# Sheet1.net
KiCad netlist of a schematic drawn in Altium Designer
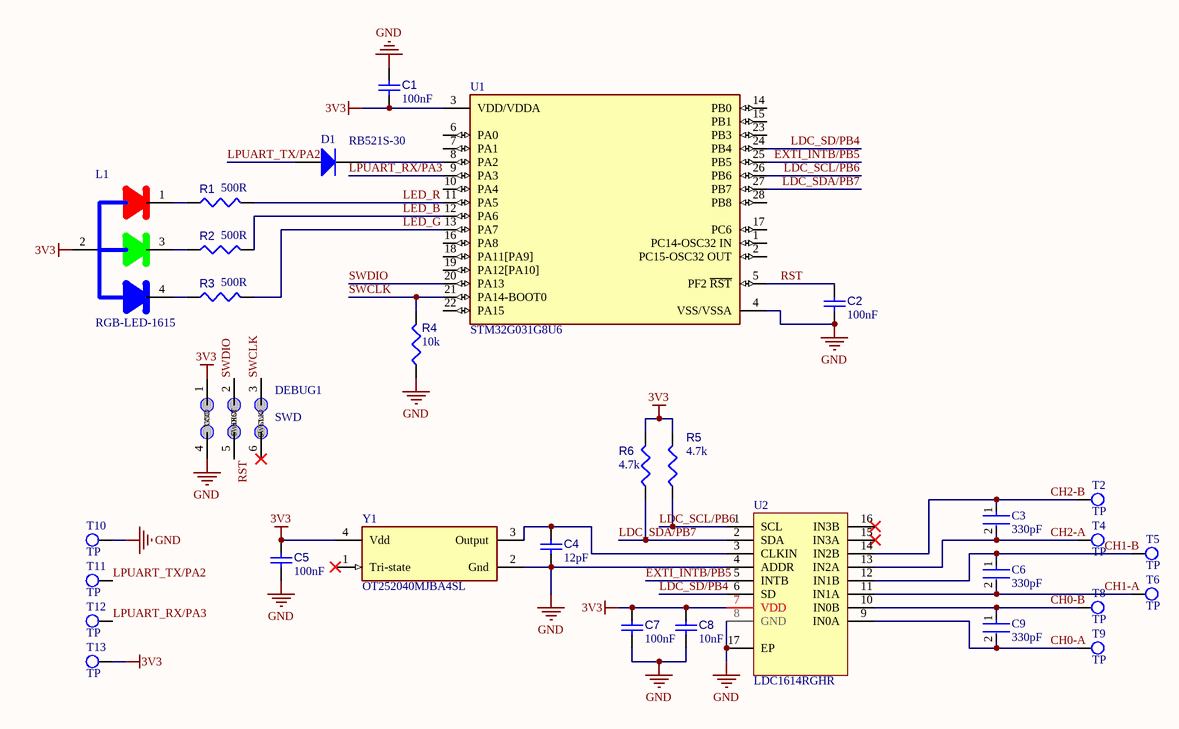
[diagram p0: Sheet1.SchDoc]

(export (version "E")
  (design (tool "Eeschema 10.0.6"))
  (components
    (comp (ref "C1")
      (value "100nF")
      (footprint "CAPC0402(1005)60_L")
      (description "Chip Capacitor, 100nF +/-20%, 10V, 0402, Thickness 0.6 mm")
      (fields (field (name "TOLERANCE") "20%") (field (name "Comment") "Capacitor 100nF +/-20% 10V 0402"))
      (libsource (lib "DigiPCBA Workspace") (part "CAP-NP-2"))
    )
    (comp (ref "C2")
      (value "100nF")
      (footprint "CAPC0402(1005)60_L")
      (description "Chip Capacitor, 100nF +/-20%, 10V, 0402, Thickness 0.6 mm")
      (fields (field (name "TOLERANCE") "20%") (field (name "Comment") "Capacitor 100nF +/-20% 10V 0402"))
      (libsource (lib "DigiPCBA Workspace") (part "CAP-NP-2"))
    )
    (comp (ref "C3")
      (value "330pF")
      (footprint "FP-C0201-AB-MFG")
      (description "C0201 18 pF C0G 30ppm/°C 5.00% 25 V")
      (fields (field (name "MANUFACTURER PART NUMBER") "C0201C180J3GACTU"))
      (libsource (lib "Altium Content Vault") (part "11868f565c42a9108669ba33697ecf6"))
    )
    (comp (ref "C4")
      (value "12pF")
      (footprint "CAPC0402(1005)33_L")
      (description "Chip Capacitor, 12pF +/-10%, 50V, 0402, Thickness 0.33 mm")
      (fields (field (name "TOLERANCE") "20%") (field (name "Comment") "Capacitor 12pF +/-10% 50V 0402"))
      (libsource (lib "DigiPCBA Workspace") (part "CAP-NP-2"))
    )
    (comp (ref "C5")
      (value "100nF")
      (footprint "CAPC0402(1005)60_L")
      (description "Chip Capacitor, 100nF +/-20%, 10V, 0402, Thickness 0.6 mm")
      (fields (field (name "TOLERANCE") "20%") (field (name "Comment") "Capacitor 100nF +/-20% 10V 0402"))
      (libsource (lib "DigiPCBA Workspace") (part "CAP-NP-2"))
    )
    (comp (ref "C6")
      (value "330pF")
      (footprint "FP-C0201-AB-MFG")
      (description "C0201 18 pF C0G 30ppm/°C 5.00% 25 V")
      (fields (field (name "MANUFACTURER PART NUMBER") "C0201C180J3GACTU"))
      (libsource (lib "Altium Content Vault") (part "11868f565c42a9108669ba33697ecf6"))
    )
    (comp (ref "C7")
      (value "100nF")
      (footprint "CAPC0402(1005)60_L")
      (description "Chip Capacitor, 100nF +/-20%, 10V, 0402, Thickness 0.6 mm")
      (fields (field (name "TOLERANCE") "20%") (field (name "Comment") "Capacitor 100nF +/-20% 10V 0402"))
      (libsource (lib "DigiPCBA Workspace") (part "CAP-NP-2"))
    )
    (comp (ref "C8")
      (value "10nF")
      (footprint "CAPC0402(1005)60_L")
      (description "Chip Capacitor, 100nF +/-20%, 10V, 0402, Thickness 0.6 mm")
      (fields (field (name "TOLERANCE") "20%") (field (name "Comment") "Capacitor 100nF +/-20% 10V 0402"))
      (libsource (lib "DigiPCBA Workspace") (part "CAP-NP-2"))
    )
    (comp (ref "C9")
      (value "330pF")
      (footprint "FP-C0201-AB-MFG")
      (description "C0201 18 pF C0G 30ppm/°C 5.00% 25 V")
      (fields (field (name "MANUFACTURER PART NUMBER") "C0201C180J3GACTU"))
      (libsource (lib "Altium Content Vault") (part "11868f565c42a9108669ba33697ecf6"))
    )
    (comp (ref "D1")
      (value "RB521S-30")
      (footprint "DIOD-SOD523-2_V")
      (description "Surface Mount Fast Switching Diode, -65 to 150 degC, 2-Pin SOD523, RoHS, Tape and Reel")
      (fields (field (name "PARTNUMBER") "1N4148WT") (field (name "MANUFACTURER") "Diodes Inc"))
      (libsource (lib "Altium Content Vault") (part "D-AK-2"))
    )
    (comp (ref "DEBUG1")
      (value "SWD")
      (footprint "DEBUG-2x3P-1.27mm Pitch")
      (description "弹簧探针烧录/调试触点")
      (libsource (lib "LG_Integrated_Library") (part "DEBUG-PogoPin-2x6P"))
    )
    (comp (ref "L1")
      (value "RGB-LED-1615")
      (footprint "RGB-LED-1615-Footprint-1")
      (description "RGB LED")
      (libsource (lib "DigiPCBA Workspace") (part "RGB-LED-1615-Symbol-1"))
    )
    (comp (ref "R1")
      (value "500R")
      (footprint "RESC0402(1005)_L")
      (description "Chip Resistor, 100 Ohms, +/-1 %, 63 mW, -55 to 155 degC, 0402")
      (fields (field (name "POWER") "63mW") (field (name "TOLERANCE") "1%"))
      (libsource (lib "DigiPCBA Workspace") (part "RES-2"))
    )
    (comp (ref "R2")
      (value "500R")
      (footprint "RESC0402(1005)_L")
      (description "Chip Resistor, 100 Ohms, +/-1 %, 63 mW, -55 to 155 degC, 0402")
      (fields (field (name "POWER") "63mW") (field (name "TOLERANCE") "1%"))
      (libsource (lib "DigiPCBA Workspace") (part "RES-2"))
    )
    (comp (ref "R3")
      (value "500R")
      (footprint "RESC0402(1005)_L")
      (description "Chip Resistor, 100 Ohms, +/-1 %, 63 mW, -55 to 155 degC, 0402")
      (fields (field (name "POWER") "63mW") (field (name "TOLERANCE") "1%"))
      (libsource (lib "DigiPCBA Workspace") (part "RES-2"))
    )
    (comp (ref "R4")
      (value "10k")
      (footprint "RESC0402(1005)_L")
      (description "Chip Resistor, 10 kOhms, +/-1 %, 63 mW, -55 to 125 degC, 0402")
      (fields (field (name "POWER") "63mW") (field (name "TOLERANCE") "1%"))
      (libsource (lib "DigiPCBA Workspace") (part "RES-2"))
    )
    (comp (ref "R5")
      (value "4.7k")
      (footprint "RESC0402(1005)_L")
      (description "Chip Resistor, 4,7 kOhms, +/-1 %, 63 mW, -55 to 155 degC, 0402")
      (fields (field (name "POWER") "63mW") (field (name "TOLERANCE") "1%"))
      (libsource (lib "DigiPCBA Workspace") (part "RES-2"))
    )
    (comp (ref "R6")
      (value "4.7k")
      (footprint "RESC0402(1005)_L")
      (description "Chip Resistor, 4,7 kOhms, +/-1 %, 63 mW, -55 to 155 degC, 0402")
      (fields (field (name "POWER") "63mW") (field (name "TOLERANCE") "1%"))
      (libsource (lib "DigiPCBA Workspace") (part "RES-2"))
    )
    (comp (ref "T2")
      (value "TP")
      (footprint "TESTPOINT-Rectangle-1.5x3")
      (description "TestPoint")
      (libsource (lib "LGSchlib") (part "TestPoint"))
    )
    (comp (ref "T4")
      (value "TP")
      (footprint "TESTPOINT-Rectangle-1.5x3")
      (description "TestPoint")
      (libsource (lib "LGSchlib") (part "TestPoint"))
    )
    (comp (ref "T5")
      (value "TP")
      (footprint "TESTPOINT-Rectangle-1.5x3")
      (description "TestPoint")
      (libsource (lib "LGSchlib") (part "TestPoint"))
    )
    (comp (ref "T6")
      (value "TP")
      (footprint "TESTPOINT-Rectangle-1.5x3")
      (description "TestPoint")
      (libsource (lib "LGSchlib") (part "TestPoint"))
    )
    (comp (ref "T8")
      (value "TP")
      (footprint "TESTPOINT-Rectangle-1.5x3")
      (description "TestPoint")
      (libsource (lib "LGSchlib") (part "TestPoint"))
    )
    (comp (ref "T9")
      (value "TP")
      (footprint "TESTPOINT-Rectangle-1.5x3")
      (description "TestPoint")
      (libsource (lib "LGSchlib") (part "TestPoint"))
    )
    (comp (ref "T10")
      (value "TP")
      (footprint "TESTPOINT-Rectangle-1.5x3")
      (description "TestPoint")
      (libsource (lib "LGSchlib") (part "TestPoint"))
    )
    (comp (ref "T11")
      (value "TP")
      (footprint "TESTPOINT-Rectangle-1.5x3")
      (description "TestPoint")
      (libsource (lib "LGSchlib") (part "TestPoint"))
    )
    (comp (ref "T12")
      (value "TP")
      (footprint "TESTPOINT-Rectangle-1.5x3")
      (description "TestPoint")
      (libsource (lib "LGSchlib") (part "TestPoint"))
    )
    (comp (ref "T13")
      (value "TP")
      (footprint "TESTPOINT-Rectangle-1.5x3")
      (description "TestPoint")
      (libsource (lib "LGSchlib") (part "TestPoint"))
    )
    (comp (ref "U1")
      (value "STM32G031G8U6")
      (footprint "FP-UFQFPN28-A0B0-MFG")
      (description "MCU 32-Bit ARM Cortex-M0+ RISC 64KB Flash 1.7V to 3.6V 28-Pin UFQFPN Tray")
      (libsource (lib "DigiPCBA Workspace") (part "fbee28bf9b321b2a381fb3d89db5bd4"))
    )
    (comp (ref "U2")
      (value "LDC1614RGHR")
      (footprint "LDC1614RGHR-Footprint-1")
      (description "4-Ch, 28-bit, high-resolution Inductance to digital converter 16-WQFN -40 to 125")
      (libsource (lib "DigiPCBA Workspace") (part "LDC1614RGHR"))
    )
    (comp (ref "Y1")
      (value "OT252040MJBA4SL")
      (footprint "FP-ECS-TXO-2520-MFG")
      (description "XTAL OSC TCXO 25.0000MHZ HCMOS")
      (libsource (lib "Altium Content Vault") (part "04cd953f3cf158082f8c09fbdb924ef"))
    )
  )
  (nets
    (net (code "1") (name "/CH0-A") (class "Default")
      (node (ref "C9") (pin "2") (pinfunction "2_2") (pintype "passive"))
      (node (ref "T9") (pin "1") (pinfunction "1_1") (pintype "passive"))
      (node (ref "U2") (pin "9") (pinfunction "IN0A_9") (pintype "passive"))
    )
    (net (code "2") (name "/CH0-B") (class "Default")
      (node (ref "C9") (pin "1") (pinfunction "1_1") (pintype "passive"))
      (node (ref "T8") (pin "1") (pinfunction "1_1") (pintype "passive"))
      (node (ref "U2") (pin "10") (pinfunction "IN0B_10") (pintype "passive"))
    )
    (net (code "3") (name "/CH1-A") (class "Default")
      (node (ref "C6") (pin "2") (pinfunction "2_2") (pintype "passive"))
      (node (ref "T6") (pin "1") (pinfunction "1_1") (pintype "passive"))
      (node (ref "U2") (pin "11") (pinfunction "IN1A_11") (pintype "passive"))
    )
    (net (code "4") (name "/CH1-B") (class "Default")
      (node (ref "C6") (pin "1") (pinfunction "1_1") (pintype "passive"))
      (node (ref "T5") (pin "1") (pinfunction "1_1") (pintype "passive"))
      (node (ref "U2") (pin "12") (pinfunction "IN1B_12") (pintype "passive"))
    )
    (net (code "5") (name "/CH2-A") (class "Default")
      (node (ref "C3") (pin "2") (pinfunction "2_2") (pintype "passive"))
      (node (ref "T4") (pin "1") (pinfunction "1_1") (pintype "passive"))
      (node (ref "U2") (pin "13") (pinfunction "IN2A_13") (pintype "passive"))
    )
    (net (code "6") (name "/CH2-B") (class "Default")
      (node (ref "C3") (pin "1") (pinfunction "1_1") (pintype "passive"))
      (node (ref "T2") (pin "1") (pinfunction "1_1") (pintype "passive"))
      (node (ref "U2") (pin "14") (pinfunction "IN2B_14") (pintype "passive"))
    )
    (net (code "7") (name "/EXTI_INTB{slash}PB5") (class "Default")
      (node (ref "U1") (pin "25") (pinfunction "PB5_25") (pintype "bidirectional"))
      (node (ref "U2") (pin "5") (pinfunction "INTB_5") (pintype "passive"))
    )
    (net (code "8") (name "/LDC_SCL{slash}PB6") (class "Default")
      (node (ref "R5") (pin "1") (pinfunction "1_1") (pintype "passive"))
      (node (ref "U1") (pin "26") (pinfunction "PB6_26") (pintype "bidirectional"))
      (node (ref "U2") (pin "1") (pinfunction "SCL_1") (pintype "passive"))
    )
    (net (code "9") (name "/LDC_SDA{slash}PB7") (class "Default")
      (node (ref "R6") (pin "1") (pinfunction "1_1") (pintype "passive"))
      (node (ref "U1") (pin "27") (pinfunction "PB7_27") (pintype "bidirectional"))
      (node (ref "U2") (pin "2") (pinfunction "SDA_2") (pintype "passive"))
    )
    (net (code "10") (name "/LDC_SD{slash}PB4") (class "Default")
      (node (ref "U1") (pin "24") (pinfunction "PB4_24") (pintype "bidirectional"))
      (node (ref "U2") (pin "6") (pinfunction "SD_6") (pintype "passive"))
    )
    (net (code "11") (name "/LED_B") (class "Default")
      (node (ref "R2") (pin "2") (pinfunction "2_2") (pintype "passive"))
      (node (ref "U1") (pin "12") (pinfunction "PA6_12") (pintype "bidirectional"))
    )
    (net (code "12") (name "/LED_G") (class "Default")
      (node (ref "R3") (pin "2") (pinfunction "2_2") (pintype "passive"))
      (node (ref "U1") (pin "13") (pinfunction "PA7_13") (pintype "bidirectional"))
    )
    (net (code "13") (name "/LED_R") (class "Default")
      (node (ref "R1") (pin "2") (pinfunction "2_2") (pintype "passive"))
      (node (ref "U1") (pin "11") (pinfunction "PA5_11") (pintype "bidirectional"))
    )
    (net (code "14") (name "/LPUART_RX{slash}PA3") (class "Default")
      (node (ref "T12") (pin "1") (pinfunction "1_1") (pintype "passive"))
      (node (ref "U1") (pin "9") (pinfunction "PA3_9") (pintype "bidirectional"))
    )
    (net (code "15") (name "/LPUART_TX{slash}PA2") (class "Default")
      (node (ref "D1") (pin "1") (pinfunction "A_1") (pintype "passive"))
      (node (ref "T11") (pin "1") (pinfunction "1_1") (pintype "passive"))
    )
    (net (code "16") (name "/RST") (class "Default")
      (node (ref "C2") (pin "2") (pinfunction "2_2") (pintype "passive"))
      (node (ref "DEBUG1") (pin "5") (pinfunction "nRST_5") (pintype "passive"))
      (node (ref "U1") (pin "5") (pinfunction "PF2_~{RST}_5") (pintype "bidirectional"))
    )
    (net (code "17") (name "/SWCLK") (class "Default")
      (node (ref "DEBUG1") (pin "3") (pinfunction "SWCLK_3") (pintype "passive"))
      (node (ref "R4") (pin "2") (pinfunction "2_2") (pintype "passive"))
      (node (ref "U1") (pin "21") (pinfunction "PA14-BOOT0_21") (pintype "bidirectional"))
    )
    (net (code "18") (name "/SWDIO") (class "Default")
      (node (ref "DEBUG1") (pin "2") (pinfunction "SWDIO_2") (pintype "passive"))
      (node (ref "U1") (pin "20") (pinfunction "PA13_20") (pintype "bidirectional"))
    )
    (net (code "19") (name "3V3") (class "Default")
      (node (ref "C1") (pin "1") (pinfunction "1_1") (pintype "passive"))
      (node (ref "C5") (pin "2") (pinfunction "2_2") (pintype "passive"))
      (node (ref "C7") (pin "2") (pinfunction "2_2") (pintype "passive"))
      (node (ref "C8") (pin "2") (pinfunction "2_2") (pintype "passive"))
      (node (ref "DEBUG1") (pin "1") (pinfunction "VCC_1") (pintype "passive"))
      (node (ref "L1") (pin "2") (pinfunction "COM+_2") (pintype "passive"))
      (node (ref "R5") (pin "2") (pinfunction "2_2") (pintype "passive"))
      (node (ref "R6") (pin "2") (pinfunction "2_2") (pintype "passive"))
      (node (ref "T13") (pin "1") (pinfunction "1_1") (pintype "passive"))
      (node (ref "U1") (pin "3") (pinfunction "VDD/VDDA_3") (pintype "power_in"))
      (node (ref "U2") (pin "7") (pinfunction "VDD_7") (pintype "passive"))
      (node (ref "Y1") (pin "4") (pinfunction "Vdd_4") (pintype "power_in"))
    )
    (net (code "20") (name "GND") (class "Default")
      (node (ref "C1") (pin "2") (pinfunction "2_2") (pintype "passive"))
      (node (ref "C2") (pin "1") (pinfunction "1_1") (pintype "passive"))
      (node (ref "C4") (pin "1") (pinfunction "1_1") (pintype "passive"))
      (node (ref "C5") (pin "1") (pinfunction "1_1") (pintype "passive"))
      (node (ref "C7") (pin "1") (pinfunction "1_1") (pintype "passive"))
      (node (ref "C8") (pin "1") (pinfunction "1_1") (pintype "passive"))
      (node (ref "DEBUG1") (pin "4") (pinfunction "GND_4") (pintype "passive"))
      (node (ref "R4") (pin "1") (pinfunction "1_1") (pintype "passive"))
      (node (ref "T10") (pin "1") (pinfunction "1_1") (pintype "passive"))
      (node (ref "U1") (pin "4") (pinfunction "VSS/VSSA_4") (pintype "power_in"))
      (node (ref "U2") (pin "17") (pinfunction "EP_17") (pintype "passive"))
      (node (ref "U2") (pin "4") (pinfunction "ADDR_4") (pintype "passive"))
      (node (ref "U2") (pin "8") (pinfunction "GND_8") (pintype "passive"))
      (node (ref "Y1") (pin "2") (pinfunction "Gnd_2") (pintype "power_in"))
    )
    (net (code "21") (name "Net-(D1-K)") (class "Default")
      (node (ref "D1") (pin "2") (pinfunction "K_2") (pintype "passive"))
      (node (ref "U1") (pin "8") (pinfunction "PA2_8") (pintype "bidirectional"))
    )
    (net (code "22") (name "Net-(L1-B)") (class "Default")
      (node (ref "L1") (pin "4") (pinfunction "B_4") (pintype "passive"))
      (node (ref "R3") (pin "1") (pinfunction "1_1") (pintype "passive"))
    )
    (net (code "23") (name "Net-(L1-G)") (class "Default")
      (node (ref "L1") (pin "3") (pinfunction "G_3") (pintype "passive"))
      (node (ref "R2") (pin "1") (pinfunction "1_1") (pintype "passive"))
    )
    (net (code "24") (name "Net-(L1-R)") (class "Default")
      (node (ref "L1") (pin "1") (pinfunction "R_1") (pintype "passive"))
      (node (ref "R1") (pin "1") (pinfunction "1_1") (pintype "passive"))
    )
    (net (code "25") (name "Net-(U2-CLKIN)") (class "Default")
      (node (ref "C4") (pin "2") (pinfunction "2_2") (pintype "passive"))
      (node (ref "U2") (pin "3") (pinfunction "CLKIN_3") (pintype "passive"))
      (node (ref "Y1") (pin "3") (pinfunction "Output_3") (pintype "tri_state"))
    )
    (net (code "26") (name "unconnected-(DEBUG1-SWO-Pad6)") (class "Default")
      (node (ref "DEBUG1") (pin "6") (pinfunction "SWO_6") (pintype "passive+no_connect"))
    )
    (net (code "27") (name "unconnected-(U1-PA0-Pad6)") (class "Default")
      (node (ref "U1") (pin "6") (pinfunction "PA0_6") (pintype "bidirectional"))
    )
    (net (code "28") (name "unconnected-(U1-PA1-Pad7)") (class "Default")
      (node (ref "U1") (pin "7") (pinfunction "PA1_7") (pintype "bidirectional"))
    )
    (net (code "29") (name "unconnected-(U1-PA4-Pad10)") (class "Default")
      (node (ref "U1") (pin "10") (pinfunction "PA4_10") (pintype "bidirectional"))
    )
    (net (code "30") (name "unconnected-(U1-PA8-Pad16)") (class "Default")
      (node (ref "U1") (pin "16") (pinfunction "PA8_16") (pintype "bidirectional"))
    )
    (net (code "31") (name "unconnected-(U1-PA11[PA9]-Pad18)") (class "Default")
      (node (ref "U1") (pin "18") (pinfunction "PA11[PA9]_18") (pintype "bidirectional"))
    )
    (net (code "32") (name "unconnected-(U1-PA12[PA10]-Pad19)") (class "Default")
      (node (ref "U1") (pin "19") (pinfunction "PA12[PA10]_19") (pintype "bidirectional"))
    )
    (net (code "33") (name "unconnected-(U1-PA15-Pad22)") (class "Default")
      (node (ref "U1") (pin "22") (pinfunction "PA15_22") (pintype "bidirectional"))
    )
    (net (code "34") (name "unconnected-(U1-PB0-Pad14)") (class "Default")
      (node (ref "U1") (pin "14") (pinfunction "PB0_14") (pintype "bidirectional"))
    )
    (net (code "35") (name "unconnected-(U1-PB1-Pad15)") (class "Default")
      (node (ref "U1") (pin "15") (pinfunction "PB1_15") (pintype "bidirectional"))
    )
    (net (code "36") (name "unconnected-(U1-PB3-Pad23)") (class "Default")
      (node (ref "U1") (pin "23") (pinfunction "PB3_23") (pintype "bidirectional"))
    )
    (net (code "37") (name "unconnected-(U1-PB8-Pad28)") (class "Default")
      (node (ref "U1") (pin "28") (pinfunction "PB8_28") (pintype "bidirectional"))
    )
    (net (code "38") (name "unconnected-(U1-PC6-Pad17)") (class "Default")
      (node (ref "U1") (pin "17") (pinfunction "PC6_17") (pintype "bidirectional"))
    )
    (net (code "39") (name "unconnected-(U1-PC14-OSC32_IN-Pad1)") (class "Default")
      (node (ref "U1") (pin "1") (pinfunction "PC14-OSC32_IN_1") (pintype "bidirectional"))
    )
    (net (code "40") (name "unconnected-(U1-PC15-OSC32_OUT-Pad2)") (class "Default")
      (node (ref "U1") (pin "2") (pinfunction "PC15-OSC32_OUT_2") (pintype "bidirectional"))
    )
    (net (code "41") (name "unconnected-(U2-IN3A-Pad15)") (class "Default")
      (node (ref "U2") (pin "15") (pinfunction "IN3A_15") (pintype "passive+no_connect"))
    )
    (net (code "42") (name "unconnected-(U2-IN3B-Pad16)") (class "Default")
      (node (ref "U2") (pin "16") (pinfunction "IN3B_16") (pintype "passive+no_connect"))
    )
    (net (code "43") (name "unconnected-(Y1-Tri-state-Pad1)") (class "Default")
      (node (ref "Y1") (pin "1") (pinfunction "Tri-state_1") (pintype "input+no_connect"))
    )
  )
)
